# Sheet2.net
KiCad netlist of a schematic drawn in Altium Designer
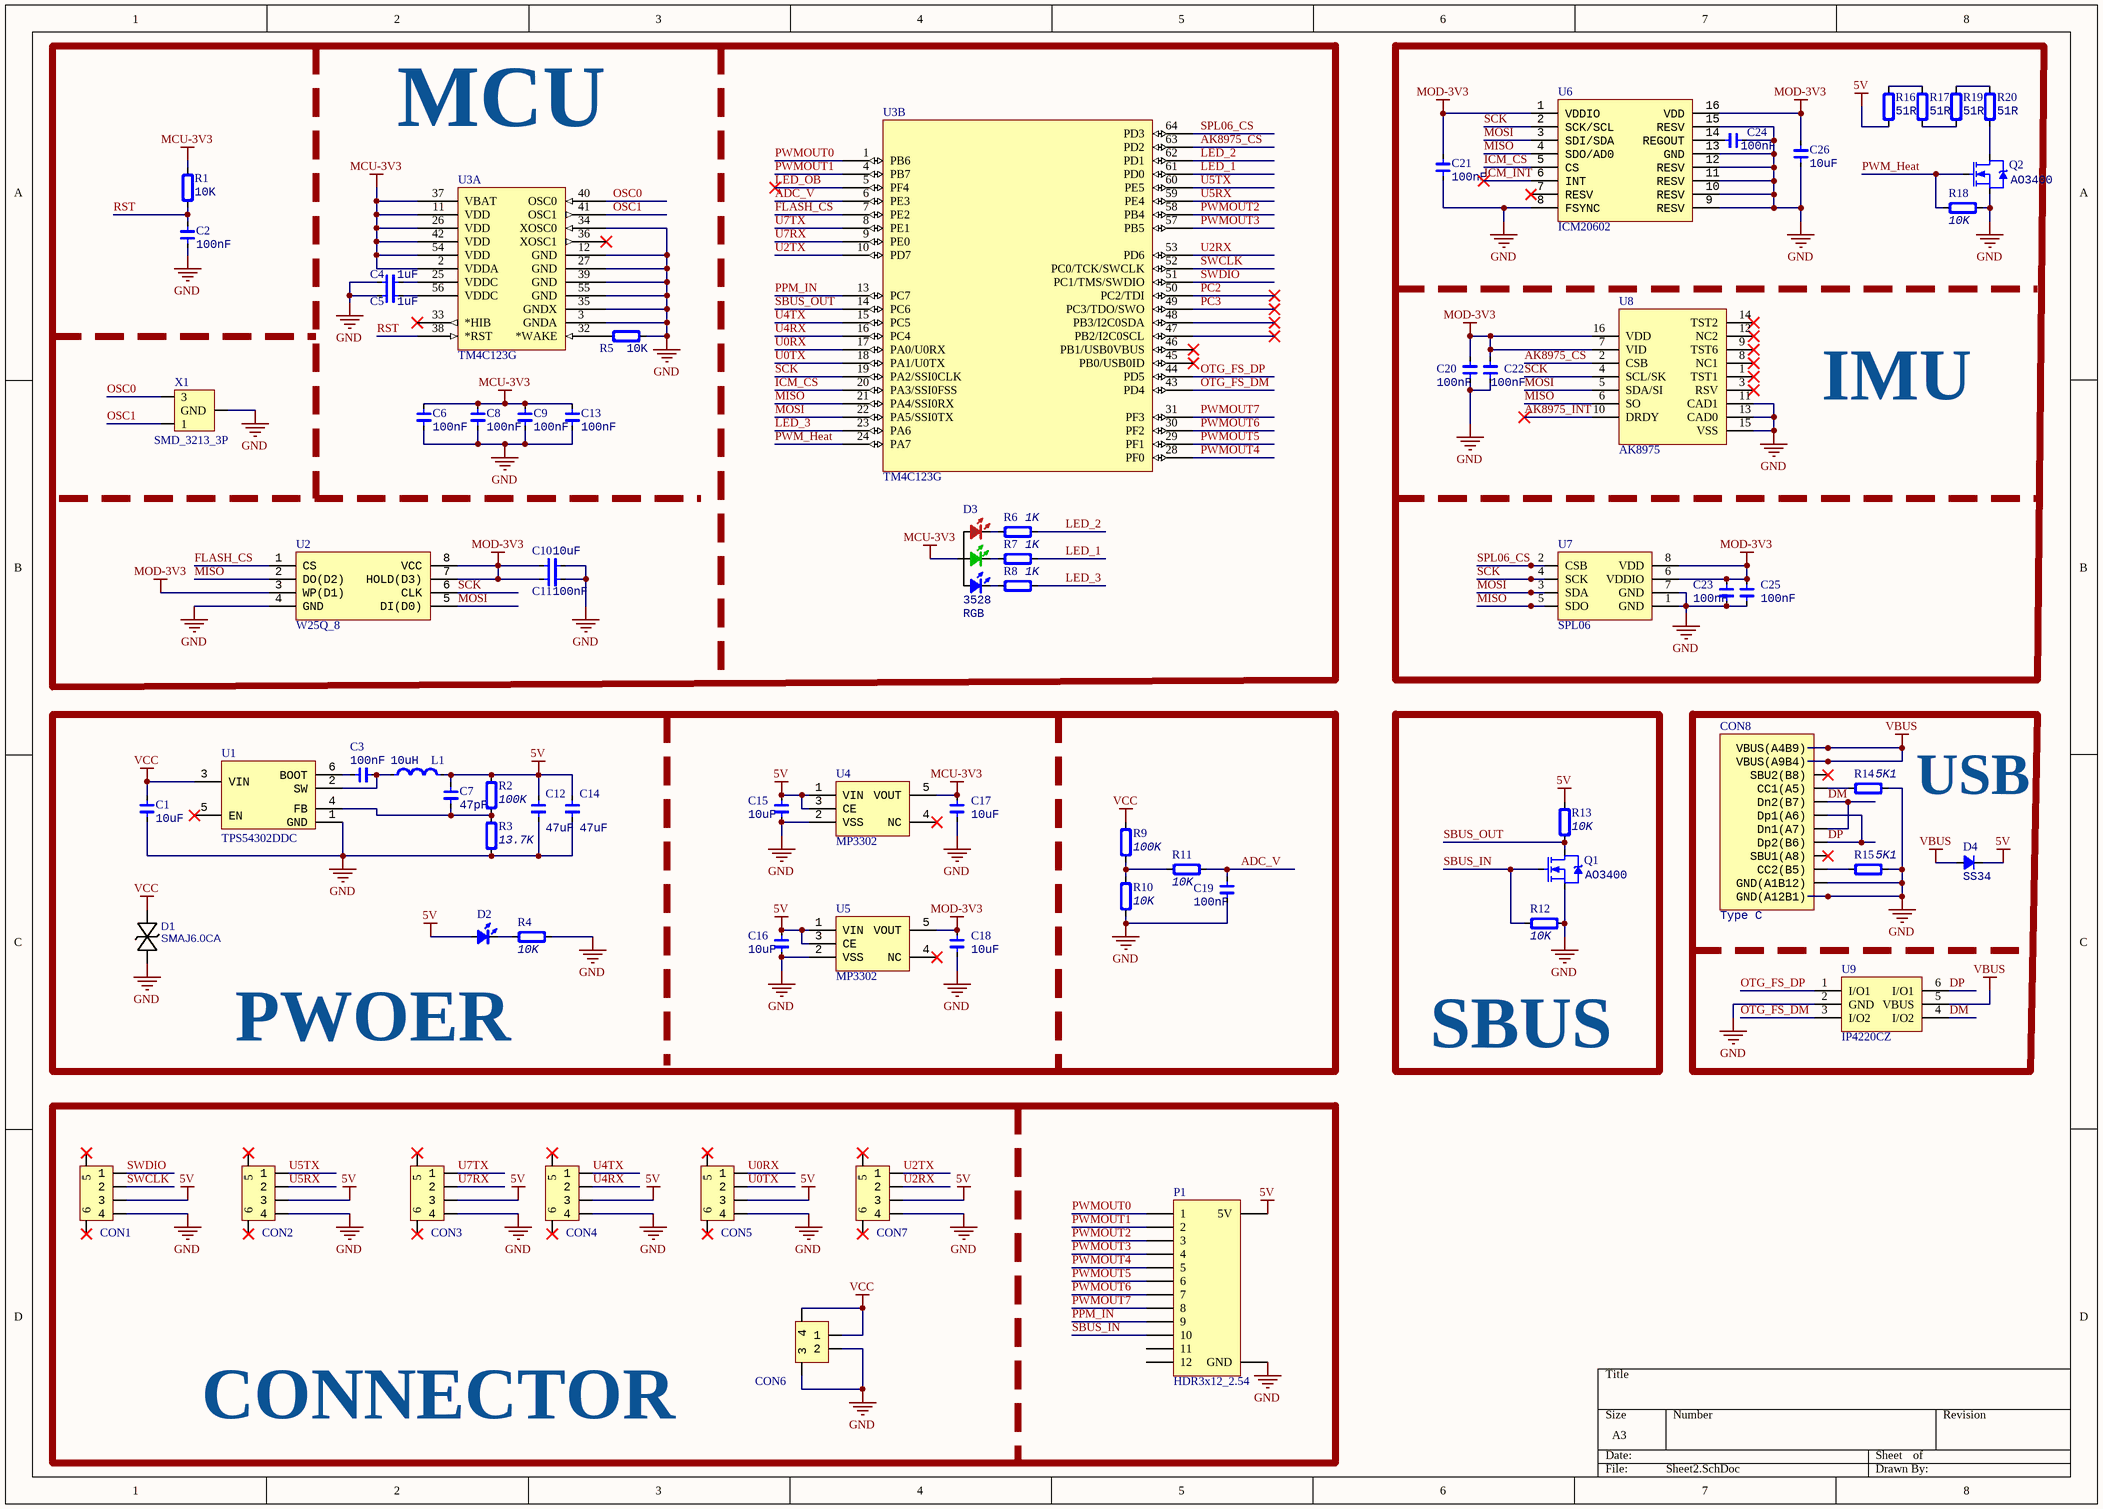
[diagram p0: Sheet2.SchDoc]

(export (version "E")
  (design (tool "Eeschema 10.0.6"))
  (components
    (comp (ref "C1")
      (value "10uF")
      (footprint "PCB_PassiveCap:CAP_0805")
      (description "Capacitor")
      (fields (field (name "Comment") "C0805"))
      (libsource (lib "SCH_Passive") (part "Cap_0805"))
    )
    (comp (ref "C2")
      (value "100nF")
      (footprint "PCB_PassiveCap:CAP_0603")
      (description "Capacitor")
      (fields (field (name "Comment") "C0603"))
      (libsource (lib "") (part "Cap_0603_1"))
    )
    (comp (ref "C3")
      (value "100nF")
      (footprint "PCB_PassiveCap:CAP_0603")
      (description "Capacitor")
      (fields (field (name "Comment") "C0603"))
      (libsource (lib "SCH_Passive") (part "Cap_0603"))
    )
    (comp (ref "C4")
      (value "1uF")
      (footprint "PCB_PassiveCap:CAP_0603")
      (description "Capacitor")
      (fields (field (name "Comment") "C0603"))
      (libsource (lib "SCH_Passive") (part "Cap_0603"))
    )
    (comp (ref "C5")
      (value "1uF")
      (footprint "PCB_PassiveCap:CAP_0603")
      (description "Capacitor")
      (fields (field (name "Comment") "C0603"))
      (libsource (lib "SCH_Passive") (part "Cap_0603"))
    )
    (comp (ref "C6")
      (value "100nF")
      (footprint "PCB_PassiveCap:CAP_0603")
      (description "Capacitor")
      (fields (field (name "Comment") "C0603"))
      (libsource (lib "") (part "Cap_0603_1"))
    )
    (comp (ref "C7")
      (value "47pF")
      (footprint "PCB_PassiveCap:CAP_0603")
      (description "Capacitor")
      (fields (field (name "Comment") "C0603"))
      (libsource (lib "") (part "Cap_0603_2"))
    )
    (comp (ref "C8")
      (value "100nF")
      (footprint "PCB_PassiveCap:CAP_0603")
      (description "Capacitor")
      (fields (field (name "Comment") "C0603"))
      (libsource (lib "") (part "Cap_0603_1"))
    )
    (comp (ref "C9")
      (value "100nF")
      (footprint "PCB_PassiveCap:CAP_0603")
      (description "Capacitor")
      (fields (field (name "Comment") "C0603"))
      (libsource (lib "") (part "Cap_0603_1"))
    )
    (comp (ref "C10")
      (value "10uF")
      (footprint "PCB_PassiveCap:CAP_0603")
      (description "Capacitor")
      (fields (field (name "Comment") "C0603"))
      (libsource (lib "") (part "Cap_0603_3"))
    )
    (comp (ref "C11")
      (value "100nF")
      (footprint "PCB_PassiveCap:CAP_0603")
      (description "Capacitor")
      (fields (field (name "Comment") "C0603"))
      (libsource (lib "SCH_Passive") (part "Cap_0603"))
    )
    (comp (ref "C12")
      (value "47uF")
      (footprint "PCB_PassiveCap:CAP_0603")
      (description "Capacitor")
      (fields (field (name "Comment") "C0603"))
      (libsource (lib "") (part "Cap_0603_1"))
    )
    (comp (ref "C13")
      (value "100nF")
      (footprint "PCB_PassiveCap:CAP_0603")
      (description "Capacitor")
      (fields (field (name "Comment") "C0603"))
      (libsource (lib "") (part "Cap_0603_1"))
    )
    (comp (ref "C14")
      (value "47uF")
      (footprint "PCB_PassiveCap:CAP_0603")
      (description "Capacitor")
      (fields (field (name "Comment") "C0603"))
      (libsource (lib "") (part "Cap_0603_1"))
    )
    (comp (ref "C15")
      (value "10uF")
      (footprint "PCB_PassiveCap:CAP_0603")
      (description "Capacitor")
      (fields (field (name "Comment") "C0603"))
      (libsource (lib "") (part "Cap_0603_1"))
    )
    (comp (ref "C16")
      (value "10uF")
      (footprint "PCB_PassiveCap:CAP_0603")
      (description "Capacitor")
      (fields (field (name "Comment") "C0603"))
      (libsource (lib "") (part "Cap_0603_1"))
    )
    (comp (ref "C17")
      (value "10uF")
      (footprint "PCB_PassiveCap:CAP_0603")
      (description "Capacitor")
      (fields (field (name "Comment") "C0603"))
      (libsource (lib "") (part "Cap_0603_1"))
    )
    (comp (ref "C18")
      (value "10uF")
      (footprint "PCB_PassiveCap:CAP_0603")
      (description "Capacitor")
      (fields (field (name "Comment") "C0603"))
      (libsource (lib "") (part "Cap_0603_1"))
    )
    (comp (ref "C19")
      (value "100nF")
      (footprint "PCB_PassiveCap:CAP_0603")
      (description "Capacitor")
      (fields (field (name "Comment") "C0603"))
      (libsource (lib "") (part "Cap_0603_2"))
    )
    (comp (ref "C20")
      (value "100nF")
      (footprint "PCB_PassiveCap:CAP_0603")
      (description "Capacitor")
      (fields (field (name "Comment") "C0603"))
      (libsource (lib "") (part "Cap_0603_2"))
    )
    (comp (ref "C21")
      (value "100nF")
      (footprint "PCB_PassiveCap:CAP_0603")
      (description "Capacitor")
      (fields (field (name "Comment") "C0603"))
      (libsource (lib "") (part "Cap_0603_2"))
    )
    (comp (ref "C22")
      (value "100nF")
      (footprint "PCB_PassiveCap:CAP_0603")
      (description "Capacitor")
      (fields (field (name "Comment") "C0603"))
      (libsource (lib "") (part "Cap_0603_2"))
    )
    (comp (ref "C23")
      (value "100nF")
      (footprint "PCB_PassiveCap:CAP_0603")
      (description "Capacitor")
      (fields (field (name "Comment") "C0603"))
      (libsource (lib "") (part "Cap_0603_2"))
    )
    (comp (ref "C24")
      (value "100nF")
      (footprint "PCB_PassiveCap:CAP_0603")
      (description "Capacitor")
      (fields (field (name "Comment") "C0603"))
      (libsource (lib "SCH_Passive") (part "Cap_0603"))
    )
    (comp (ref "C25")
      (value "100nF")
      (footprint "PCB_PassiveCap:CAP_0603")
      (description "Capacitor")
      (fields (field (name "Comment") "C0603"))
      (libsource (lib "") (part "Cap_0603_2"))
    )
    (comp (ref "C26")
      (value "10uF")
      (footprint "PCB_PassiveCap:CAP_0603")
      (description "Capacitor")
      (fields (field (name "Comment") "C0603"))
      (libsource (lib "") (part "Cap_0603_2"))
    )
    (comp (ref "CON1")
      (value "GH1.25_4P")
      (footprint "GH1.25_4P卧贴")
      (description "GH")
      (libsource (lib "SCH_Connector") (part "GH1.25_4P"))
    )
    (comp (ref "CON2")
      (value "GH1.25_4P")
      (footprint "GH1.25_4P卧贴")
      (description "GH")
      (libsource (lib "SCH_Connector") (part "GH1.25_4P"))
    )
    (comp (ref "CON3")
      (value "GH1.25_4P")
      (footprint "GH1.25_4P卧贴")
      (description "GH")
      (libsource (lib "SCH_Connector") (part "GH1.25_4P"))
    )
    (comp (ref "CON4")
      (value "GH1.25_4P")
      (footprint "GH1.25_4P卧贴")
      (description "GH")
      (libsource (lib "SCH_Connector") (part "GH1.25_4P"))
    )
    (comp (ref "CON5")
      (value "GH1.25_4P")
      (footprint "GH1.25_4P卧贴")
      (description "GH")
      (libsource (lib "SCH_Connector") (part "GH1.25_4P"))
    )
    (comp (ref "CON6")
      (value "GH1.25_2P")
      (footprint "GH1.25-2P")
      (description "GH")
      (libsource (lib "SCH_Connector") (part "GH1.25_2P"))
    )
    (comp (ref "CON7")
      (value "GH1.25_4P")
      (footprint "GH1.25_4P卧贴")
      (description "GH")
      (libsource (lib "SCH_Connector") (part "GH1.25_4P"))
    )
    (comp (ref "CON8")
      (value "Type C")
      (footprint "USB_TypeC_SMD_16P")
      (description "USB")
      (fields (field (name "Comment") "USB Type C"))
      (libsource (lib "SCH_USB") (part "USB_TypeC_16P"))
    )
    (comp (ref "D1")
      (value "SMAJ6.0CA")
      (footprint "DO-214AC")
      (description "SMAJ6.0CA_C698928")
      (fields (field (name "BOM_SUPPLIER PART") "C698928") (field (name "CONTRIBUTOR") "LCSC"))
      (libsource (lib "封装库") (part "SMAJ6.0CA"))
    )
    (comp (ref "D2")
      (value "D0603")
      (footprint "PCB_ActiveLED:LED_0603_RED")
      (description "LED")
      (libsource (lib "SCH_Active") (part "LED_0603"))
    )
    (comp (ref "D3")
      (value "RGB")
      (footprint "PCB_ActiveLED:LED_3528_RGB")
      (description "LED")
      (fields (field (name "TYPE") "3528") (field (name "Comment") "D3528"))
      (libsource (lib "SCH_Active") (part "LED_3528_RGB"))
    )
    (comp (ref "D4")
      (value "SS34")
      (footprint "PCB_ActiveDIO:DO-214AC")
      (description "Diode")
      (libsource (lib "SCH_Active") (part "Diode_SMA"))
    )
    (comp (ref "L1")
      (value "10uH")
      (footprint "IND_0630")
      (description "Inductor")
      (fields (field (name "Comment") "H1008"))
      (libsource (lib "SCH_Passive") (part "Ind_0630"))
    )
    (comp (ref "P1")
      (value "HDR3x12_2.54")
      (footprint "HDR3x12_2.54")
      (libsource (lib "SCH_ConnectorHDR") (part "HDR3x12_2.54"))
    )
    (comp (ref "Q1")
      (value "AO3400")
      (footprint "SOT23-3")
      (description "MOSFET")
      (libsource (lib "SCH_Active") (part "MOSFET_N"))
    )
    (comp (ref "Q2")
      (value "AO3400")
      (footprint "SOT23-3")
      (description "MOSFET")
      (libsource (lib "SCH_Active") (part "MOSFET_N"))
    )
    (comp (ref "R1")
      (value "10K")
      (footprint "PCB_PassiveRes:RES_0603")
      (description "Resistor")
      (fields (field (name "Comment") "R0603"))
      (libsource (lib "SCH_Passive") (part "Res_0603"))
    )
    (comp (ref "R2")
      (value "100K")
      (footprint "PCB_PassiveRes:RES_0603")
      (description "Resistor")
      (fields (field (name "Comment") "R0603"))
      (libsource (lib "SCH_Passive") (part "Res_0603"))
    )
    (comp (ref "R3")
      (value "13.7K")
      (footprint "PCB_PassiveRes:RES_0603")
      (description "Resistor")
      (fields (field (name "Comment") "R0603"))
      (libsource (lib "SCH_Passive") (part "Res_0603"))
    )
    (comp (ref "R4")
      (value "10K")
      (footprint "PCB_PassiveRes:RES_0603")
      (description "Resistor")
      (fields (field (name "Comment") "R0603"))
      (libsource (lib "SCH_Passive") (part "Res_0603"))
    )
    (comp (ref "R5")
      (value "10K")
      (footprint "PCB_PassiveRes:RES_0603")
      (description "Resistor")
      (fields (field (name "Comment") "R0603"))
      (libsource (lib "SCH_Passive") (part "Res_0603"))
    )
    (comp (ref "R6")
      (value "1K")
      (footprint "PCB_PassiveRes:RES_0603")
      (description "Resistor")
      (fields (field (name "Comment") "R0603"))
      (libsource (lib "SCH_Passive") (part "Res_0603"))
    )
    (comp (ref "R7")
      (value "1K")
      (footprint "PCB_PassiveRes:RES_0603")
      (description "Resistor")
      (fields (field (name "Comment") "R0603"))
      (libsource (lib "SCH_Passive") (part "Res_0603"))
    )
    (comp (ref "R8")
      (value "1K")
      (footprint "PCB_PassiveRes:RES_0603")
      (description "Resistor")
      (fields (field (name "Comment") "R0603"))
      (libsource (lib "SCH_Passive") (part "Res_0603"))
    )
    (comp (ref "R9")
      (value "100K")
      (footprint "PCB_PassiveRes:RES_0603")
      (description "Resistor")
      (fields (field (name "Comment") "R0603"))
      (libsource (lib "SCH_Passive") (part "Res_0603"))
    )
    (comp (ref "R10")
      (value "10K")
      (footprint "PCB_PassiveRes:RES_0603")
      (description "Resistor")
      (fields (field (name "Comment") "R0603"))
      (libsource (lib "SCH_Passive") (part "Res_0603"))
    )
    (comp (ref "R11")
      (value "10K")
      (footprint "PCB_PassiveRes:RES_0603")
      (description "Resistor")
      (fields (field (name "Comment") "R0603"))
      (libsource (lib "SCH_Passive") (part "Res_0603"))
    )
    (comp (ref "R12")
      (value "10K")
      (footprint "PCB_PassiveRes:RES_0603")
      (description "Resistor")
      (fields (field (name "Comment") "R0603"))
      (libsource (lib "SCH_Passive") (part "Res_0603"))
    )
    (comp (ref "R13")
      (value "10K")
      (footprint "PCB_PassiveRes:RES_0603")
      (description "Resistor")
      (fields (field (name "Comment") "R0603"))
      (libsource (lib "SCH_Passive") (part "Res_0603"))
    )
    (comp (ref "R14")
      (value "5K1")
      (footprint "PCB_PassiveRes:RES_0603")
      (description "Resistor")
      (fields (field (name "Comment") "R0603"))
      (libsource (lib "SCH_Passive") (part "Res_0603"))
    )
    (comp (ref "R15")
      (value "5K1")
      (footprint "PCB_PassiveRes:RES_0603")
      (description "Resistor")
      (fields (field (name "Comment") "R0603"))
      (libsource (lib "SCH_Passive") (part "Res_0603"))
    )
    (comp (ref "R16")
      (value "51R")
      (footprint "PCB_PassiveRes:RES_0805")
      (description "Resistor")
      (fields (field (name "Comment") "R0805"))
      (libsource (lib "SCH_Passive") (part "Res_0805"))
    )
    (comp (ref "R17")
      (value "51R")
      (footprint "PCB_PassiveRes:RES_0805")
      (description "Resistor")
      (fields (field (name "Comment") "R0805"))
      (libsource (lib "SCH_Passive") (part "Res_0805"))
    )
    (comp (ref "R18")
      (value "10K")
      (footprint "PCB_PassiveRes:RES_0603")
      (description "Resistor")
      (fields (field (name "Comment") "R0603"))
      (libsource (lib "SCH_Passive") (part "Res_0603"))
    )
    (comp (ref "R19")
      (value "51R")
      (footprint "PCB_PassiveRes:RES_0805")
      (description "Resistor")
      (fields (field (name "Comment") "R0805"))
      (libsource (lib "SCH_Passive") (part "Res_0805"))
    )
    (comp (ref "R20")
      (value "51R")
      (footprint "PCB_PassiveRes:RES_0805")
      (description "Resistor")
      (fields (field (name "Comment") "R0805"))
      (libsource (lib "SCH_Passive") (part "Res_0805"))
    )
    (comp (ref "U1")
      (value "TPS54302DDC")
      (footprint "SOT23-6")
      (description "Power")
      (libsource (lib "SCH_Power") (part "TPS54302DDC"))
    )
    (comp (ref "U2")
      (value "W25Q_8")
      (footprint "PCB_IntegratedCircuit:SON_P1.27H_8")
      (description "FLASH")
      (libsource (lib "SCH_IntegratedCircuit") (part "W25Q_8"))
    )
    (comp (ref "U3")
      (value "TM4C123G")
      (footprint "LQFP_P0.5_64")
      (libsource (lib "SCH_Microcontroller") (part "TM4C123G"))
    )
    (comp (ref "U4")
      (value "MP3302")
      (footprint "PCB_IntegratedCircuit:SOT23-5")
      (description "WLED Driver")
      (libsource (lib "SCH_Power") (part "HX9133"))
    )
    (comp (ref "U5")
      (value "MP3302")
      (footprint "PCB_IntegratedCircuit:SOT23-5")
      (description "WLED Driver")
      (libsource (lib "SCH_Power") (part "HX9133"))
    )
    (comp (ref "U6")
      (value "ICM20602")
      (footprint "LGA_P0.5_16")
      (description "Sensor Motion")
      (libsource (lib "SCH_Sensor") (part "ICM20602"))
    )
    (comp (ref "U7") (value "SPL06") (footprint "SMD_8P-2x2.5") (libsource (lib "SCH_Sensor") (part "SPL06")))
    (comp (ref "U8")
      (value "AK8975")
      (footprint "QFN_P0.65_16")
      (libsource (lib "SCH_Sensor") (part "AK8975"))
    )
    (comp (ref "U9") (value "IP4220CZ") (footprint "SOT23-6") (libsource (lib "SCH_USB") (part "USB_ESD")))
    (comp (ref "X1")
      (value "SMD_3213_3P")
      (footprint "XT_3213_3")
      (description "Crystal Oscillator")
      (libsource (lib "SCH_Oscillator") (part "SMD_3213_3P"))
    )
  )
  (nets
    (net (code "1") (name "/ADC_V") (class "Default")
      (node (ref "C19") (pin "1") (pinfunction "1_1") (pintype "passive"))
      (node (ref "R11") (pin "1") (pinfunction "1_1") (pintype "passive"))
      (node (ref "U3") (pin "6") (pinfunction "PE3_6") (pintype "bidirectional"))
    )
    (net (code "2") (name "/AK8975_CS") (class "Default")
      (node (ref "U3") (pin "63") (pinfunction "PD2_63") (pintype "bidirectional"))
      (node (ref "U8") (pin "2") (pinfunction "CSB_2") (pintype "passive"))
    )
    (net (code "3") (name "/AK8975_INT") (class "Default")
      (node (ref "U8") (pin "10") (pinfunction "DRDY_10") (pintype "passive+no_connect"))
    )
    (net (code "4") (name "/DM") (class "Default")
      (node (ref "CON8") (pin "5") (pinfunction "Dn2(B7)_5") (pintype "passive"))
      (node (ref "CON8") (pin "7") (pinfunction "Dn1(A7)_7") (pintype "passive"))
      (node (ref "U9") (pin "4") (pinfunction "I/O2_4") (pintype "passive"))
    )
    (net (code "5") (name "/DP") (class "Default")
      (node (ref "CON8") (pin "6") (pinfunction "Dp1(A6)_6") (pintype "passive"))
      (node (ref "CON8") (pin "8") (pinfunction "Dp2(B6)_8") (pintype "passive"))
      (node (ref "U9") (pin "6") (pinfunction "I/O1_6") (pintype "passive"))
    )
    (net (code "6") (name "/FLASH_CS") (class "Default")
      (node (ref "U2") (pin "1") (pinfunction "CS_1") (pintype "passive"))
      (node (ref "U3") (pin "7") (pinfunction "PE2_7") (pintype "bidirectional"))
    )
    (net (code "7") (name "/ICM_CS") (class "Default")
      (node (ref "U3") (pin "20") (pinfunction "PA3/SSI0FSS_20") (pintype "bidirectional"))
      (node (ref "U6") (pin "5") (pinfunction "CS_5") (pintype "passive"))
    )
    (net (code "8") (name "/ICM_INT") (class "Default")
      (node (ref "U6") (pin "6") (pinfunction "INT_6") (pintype "passive+no_connect"))
    )
    (net (code "9") (name "/LED_1") (class "Default")
      (node (ref "R7") (pin "1") (pinfunction "1_1") (pintype "passive"))
      (node (ref "U3") (pin "61") (pinfunction "PD0_61") (pintype "bidirectional"))
    )
    (net (code "10") (name "/LED_2") (class "Default")
      (node (ref "R6") (pin "1") (pinfunction "1_1") (pintype "passive"))
      (node (ref "U3") (pin "62") (pinfunction "PD1_62") (pintype "bidirectional"))
    )
    (net (code "11") (name "/LED_3") (class "Default")
      (node (ref "R8") (pin "1") (pinfunction "1_1") (pintype "passive"))
      (node (ref "U3") (pin "23") (pinfunction "PA6_23") (pintype "bidirectional"))
    )
    (net (code "12") (name "/LED_OB") (class "Default")
      (node (ref "U3") (pin "5") (pinfunction "PF4_5") (pintype "bidirectional+no_connect"))
    )
    (net (code "13") (name "/MISO") (class "Default")
      (node (ref "U2") (pin "2") (pinfunction "DO(D2)_2") (pintype "passive"))
      (node (ref "U3") (pin "21") (pinfunction "PA4/SSI0RX_21") (pintype "bidirectional"))
      (node (ref "U6") (pin "4") (pinfunction "SDO/AD0_4") (pintype "passive"))
      (node (ref "U7") (pin "5") (pinfunction "SDO_5") (pintype "passive"))
      (node (ref "U8") (pin "6") (pinfunction "SO_6") (pintype "passive"))
    )
    (net (code "14") (name "/MOSI") (class "Default")
      (node (ref "U2") (pin "5") (pinfunction "DI(D0)_5") (pintype "passive"))
      (node (ref "U3") (pin "22") (pinfunction "PA5/SSI0TX_22") (pintype "bidirectional"))
      (node (ref "U6") (pin "3") (pinfunction "SDI/SDA_3") (pintype "passive"))
      (node (ref "U7") (pin "3") (pinfunction "SDA_3") (pintype "passive"))
      (node (ref "U8") (pin "5") (pinfunction "SDA/SI_5") (pintype "passive"))
    )
    (net (code "15") (name "/OSC0") (class "Default")
      (node (ref "U3") (pin "40") (pinfunction "OSC0_40") (pintype "input"))
      (node (ref "X1") (pin "3") (pinfunction "3_3") (pintype "passive"))
    )
    (net (code "16") (name "/OSC1") (class "Default")
      (node (ref "U3") (pin "41") (pinfunction "OSC1_41") (pintype "output"))
      (node (ref "X1") (pin "1") (pinfunction "1_1") (pintype "passive"))
    )
    (net (code "17") (name "/OTG_FS_DM") (class "Default")
      (node (ref "U3") (pin "43") (pinfunction "PD4_43") (pintype "bidirectional"))
      (node (ref "U9") (pin "3") (pinfunction "I/O2_3") (pintype "passive"))
    )
    (net (code "18") (name "/OTG_FS_DP") (class "Default")
      (node (ref "U3") (pin "44") (pinfunction "PD5_44") (pintype "bidirectional"))
      (node (ref "U9") (pin "1") (pinfunction "I/O1_1") (pintype "passive"))
    )
    (net (code "19") (name "/PC2") (class "Default")
      (node (ref "U3") (pin "50") (pinfunction "PC2/TDI_50") (pintype "bidirectional+no_connect"))
    )
    (net (code "20") (name "/PC3") (class "Default")
      (node (ref "U3") (pin "49") (pinfunction "PC3/TDO/SWO_49") (pintype "bidirectional+no_connect"))
    )
    (net (code "21") (name "/PPM_IN") (class "Default")
      (node (ref "P1") (pin "9") (pinfunction "9_9") (pintype "passive"))
      (node (ref "U3") (pin "13") (pinfunction "PC7_13") (pintype "bidirectional"))
    )
    (net (code "22") (name "/PWMOUT0") (class "Default")
      (node (ref "P1") (pin "1") (pinfunction "1_1") (pintype "passive"))
      (node (ref "U3") (pin "1") (pinfunction "PB6_1") (pintype "bidirectional"))
    )
    (net (code "23") (name "/PWMOUT1") (class "Default")
      (node (ref "P1") (pin "2") (pinfunction "2_2") (pintype "passive"))
      (node (ref "U3") (pin "4") (pinfunction "PB7_4") (pintype "bidirectional"))
    )
    (net (code "24") (name "/PWMOUT2") (class "Default")
      (node (ref "P1") (pin "3") (pinfunction "3_3") (pintype "passive"))
      (node (ref "U3") (pin "58") (pinfunction "PB4_58") (pintype "bidirectional"))
    )
    (net (code "25") (name "/PWMOUT3") (class "Default")
      (node (ref "P1") (pin "4") (pinfunction "4_4") (pintype "passive"))
      (node (ref "U3") (pin "57") (pinfunction "PB5_57") (pintype "bidirectional"))
    )
    (net (code "26") (name "/PWMOUT4") (class "Default")
      (node (ref "P1") (pin "5") (pinfunction "5_5") (pintype "passive"))
      (node (ref "U3") (pin "28") (pinfunction "PF0_28") (pintype "bidirectional"))
    )
    (net (code "27") (name "/PWMOUT5") (class "Default")
      (node (ref "P1") (pin "6") (pinfunction "6_6") (pintype "passive"))
      (node (ref "U3") (pin "29") (pinfunction "PF1_29") (pintype "bidirectional"))
    )
    (net (code "28") (name "/PWMOUT6") (class "Default")
      (node (ref "P1") (pin "7") (pinfunction "7_7") (pintype "passive"))
      (node (ref "U3") (pin "30") (pinfunction "PF2_30") (pintype "bidirectional"))
    )
    (net (code "29") (name "/PWMOUT7") (class "Default")
      (node (ref "P1") (pin "8") (pinfunction "8_8") (pintype "passive"))
      (node (ref "U3") (pin "31") (pinfunction "PF3_31") (pintype "bidirectional"))
    )
    (net (code "30") (name "/PWM_Heat") (class "Default")
      (node (ref "Q2") (pin "2") (pinfunction "G_2") (pintype "passive"))
      (node (ref "R18") (pin "1") (pinfunction "1_1") (pintype "passive"))
      (node (ref "U3") (pin "24") (pinfunction "PA7_24") (pintype "bidirectional"))
    )
    (net (code "31") (name "/RST") (class "Default")
      (node (ref "C2") (pin "2") (pinfunction "2_2") (pintype "passive"))
      (node (ref "R1") (pin "1") (pinfunction "1_1") (pintype "passive"))
      (node (ref "U3") (pin "38") (pinfunction "*RST_38") (pintype "input"))
    )
    (net (code "32") (name "/SBUS_IN") (class "Default")
      (node (ref "P1") (pin "10") (pinfunction "10_10") (pintype "passive"))
      (node (ref "Q1") (pin "2") (pinfunction "G_2") (pintype "passive"))
      (node (ref "R12") (pin "1") (pinfunction "1_1") (pintype "passive"))
    )
    (net (code "33") (name "/SBUS_OUT") (class "Default")
      (node (ref "Q1") (pin "3") (pinfunction "D_3") (pintype "passive"))
      (node (ref "R13") (pin "1") (pinfunction "1_1") (pintype "passive"))
      (node (ref "U3") (pin "14") (pinfunction "PC6_14") (pintype "bidirectional"))
    )
    (net (code "34") (name "/SCK") (class "Default")
      (node (ref "U2") (pin "6") (pinfunction "CLK_6") (pintype "passive"))
      (node (ref "U3") (pin "19") (pinfunction "PA2/SSI0CLK_19") (pintype "bidirectional"))
      (node (ref "U6") (pin "2") (pinfunction "SCK/SCL_2") (pintype "passive"))
      (node (ref "U7") (pin "4") (pinfunction "SCK_4") (pintype "passive"))
      (node (ref "U8") (pin "4") (pinfunction "SCL/SK_4") (pintype "passive"))
    )
    (net (code "35") (name "/SPL06_CS") (class "Default")
      (node (ref "U3") (pin "64") (pinfunction "PD3_64") (pintype "bidirectional"))
      (node (ref "U7") (pin "2") (pinfunction "CSB_2") (pintype "passive"))
    )
    (net (code "36") (name "/SWCLK") (class "Default")
      (node (ref "CON1") (pin "2") (pinfunction "2_2") (pintype "passive"))
      (node (ref "U3") (pin "52") (pinfunction "PC0/TCK/SWCLK_52") (pintype "bidirectional"))
    )
    (net (code "37") (name "/SWDIO") (class "Default")
      (node (ref "CON1") (pin "1") (pinfunction "1_1") (pintype "passive"))
      (node (ref "U3") (pin "51") (pinfunction "PC1/TMS/SWDIO_51") (pintype "bidirectional"))
    )
    (net (code "38") (name "/U0RX") (class "Default")
      (node (ref "CON5") (pin "1") (pinfunction "1_1") (pintype "passive"))
      (node (ref "U3") (pin "17") (pinfunction "PA0/U0RX_17") (pintype "bidirectional"))
    )
    (net (code "39") (name "/U0TX") (class "Default")
      (node (ref "CON5") (pin "2") (pinfunction "2_2") (pintype "passive"))
      (node (ref "U3") (pin "18") (pinfunction "PA1/U0TX_18") (pintype "bidirectional"))
    )
    (net (code "40") (name "/U2RX") (class "Default")
      (node (ref "CON7") (pin "2") (pinfunction "2_2") (pintype "passive"))
      (node (ref "U3") (pin "53") (pinfunction "PD6_53") (pintype "bidirectional"))
    )
    (net (code "41") (name "/U2TX") (class "Default")
      (node (ref "CON7") (pin "1") (pinfunction "1_1") (pintype "passive"))
      (node (ref "U3") (pin "10") (pinfunction "PD7_10") (pintype "bidirectional"))
    )
    (net (code "42") (name "/U4RX") (class "Default")
      (node (ref "CON4") (pin "2") (pinfunction "2_2") (pintype "passive"))
      (node (ref "U3") (pin "16") (pinfunction "PC4_16") (pintype "bidirectional"))
    )
    (net (code "43") (name "/U4TX") (class "Default")
      (node (ref "CON4") (pin "1") (pinfunction "1_1") (pintype "passive"))
      (node (ref "U3") (pin "15") (pinfunction "PC5_15") (pintype "bidirectional"))
    )
    (net (code "44") (name "/U5RX") (class "Default")
      (node (ref "CON2") (pin "2") (pinfunction "2_2") (pintype "passive"))
      (node (ref "U3") (pin "59") (pinfunction "PE4_59") (pintype "bidirectional"))
    )
    (net (code "45") (name "/U5TX") (class "Default")
      (node (ref "CON2") (pin "1") (pinfunction "1_1") (pintype "passive"))
      (node (ref "U3") (pin "60") (pinfunction "PE5_60") (pintype "bidirectional"))
    )
    (net (code "46") (name "/U7RX") (class "Default")
      (node (ref "CON3") (pin "2") (pinfunction "2_2") (pintype "passive"))
      (node (ref "U3") (pin "9") (pinfunction "PE0_9") (pintype "bidirectional"))
    )
    (net (code "47") (name "/U7TX") (class "Default")
      (node (ref "CON3") (pin "1") (pinfunction "1_1") (pintype "passive"))
      (node (ref "U3") (pin "8") (pinfunction "PE1_8") (pintype "bidirectional"))
    )
    (net (code "48") (name "5V") (class "Default")
      (node (ref "C12") (pin "2") (pinfunction "2_2") (pintype "passive"))
      (node (ref "C14") (pin "2") (pinfunction "2_2") (pintype "passive"))
      (node (ref "C15") (pin "2") (pinfunction "2_2") (pintype "passive"))
      (node (ref "C16") (pin "2") (pinfunction "2_2") (pintype "passive"))
      (node (ref "C7") (pin "1") (pinfunction "1_1") (pintype "passive"))
      (node (ref "CON1") (pin "3") (pinfunction "3_3") (pintype "passive"))
      (node (ref "CON2") (pin "3") (pinfunction "3_3") (pintype "passive"))
      (node (ref "CON3") (pin "3") (pinfunction "3_3") (pintype "passive"))
      (node (ref "CON4") (pin "3") (pinfunction "3_3") (pintype "passive"))
      (node (ref "CON5") (pin "3") (pinfunction "3_3") (pintype "passive"))
      (node (ref "CON7") (pin "3") (pinfunction "3_3") (pintype "passive"))
      (node (ref "D2") (pin "1") (pinfunction "A_1") (pintype "passive"))
      (node (ref "D4") (pin "2") (pinfunction "K_2") (pintype "passive"))
      (node (ref "L1") (pin "2") (pinfunction "2_2") (pintype "passive"))
      (node (ref "P1") (pin "13") (pinfunction "5V_13") (pintype "passive"))
      (node (ref "R13") (pin "2") (pinfunction "2_2") (pintype "passive"))
      (node (ref "R16") (pin "1") (pinfunction "1_1") (pintype "passive"))
      (node (ref "R2") (pin "2") (pinfunction "2_2") (pintype "passive"))
      (node (ref "U4") (pin "1") (pinfunction "VIN_1") (pintype "passive"))
      (node (ref "U4") (pin "3") (pinfunction "CE_3") (pintype "passive"))
      (node (ref "U5") (pin "1") (pinfunction "VIN_1") (pintype "passive"))
      (node (ref "U5") (pin "3") (pinfunction "CE_3") (pintype "passive"))
    )
    (net (code "49") (name "GND") (class "Default")
      (node (ref "C1") (pin "1") (pinfunction "1_1") (pintype "passive"))
      (node (ref "C10") (pin "2") (pinfunction "2_2") (pintype "passive"))
      (node (ref "C11") (pin "1") (pinfunction "1_1") (pintype "passive"))
      (node (ref "C12") (pin "1") (pinfunction "1_1") (pintype "passive"))
      (node (ref "C13") (pin "1") (pinfunction "1_1") (pintype "passive"))
      (node (ref "C14") (pin "1") (pinfunction "1_1") (pintype "passive"))
      (node (ref "C15") (pin "1") (pinfunction "1_1") (pintype "passive"))
      (node (ref "C16") (pin "1") (pinfunction "1_1") (pintype "passive"))
      (node (ref "C17") (pin "1") (pinfunction "1_1") (pintype "passive"))
      (node (ref "C18") (pin "1") (pinfunction "1_1") (pintype "passive"))
      (node (ref "C19") (pin "2") (pinfunction "2_2") (pintype "passive"))
      (node (ref "C2") (pin "1") (pinfunction "1_1") (pintype "passive"))
      (node (ref "C20") (pin "2") (pinfunction "2_2") (pintype "passive"))
      (node (ref "C21") (pin "2") (pinfunction "2_2") (pintype "passive"))
      (node (ref "C22") (pin "2") (pinfunction "2_2") (pintype "passive"))
      (node (ref "C23") (pin "2") (pinfunction "2_2") (pintype "passive"))
      (node (ref "C24") (pin "1") (pinfunction "1_1") (pintype "passive"))
      (node (ref "C25") (pin "2") (pinfunction "2_2") (pintype "passive"))
      (node (ref "C26") (pin "2") (pinfunction "2_2") (pintype "passive"))
      (node (ref "C4") (pin "2") (pinfunction "2_2") (pintype "passive"))
      (node (ref "C5") (pin "2") (pinfunction "2_2") (pintype "passive"))
      (node (ref "C6") (pin "1") (pinfunction "1_1") (pintype "passive"))
      (node (ref "C8") (pin "1") (pinfunction "1_1") (pintype "passive"))
      (node (ref "C9") (pin "1") (pinfunction "1_1") (pintype "passive"))
      (node (ref "CON1") (pin "4") (pinfunction "4_4") (pintype "passive"))
      (node (ref "CON2") (pin "4") (pinfunction "4_4") (pintype "passive"))
      (node (ref "CON3") (pin "4") (pinfunction "4_4") (pintype "passive"))
      (node (ref "CON4") (pin "4") (pinfunction "4_4") (pintype "passive"))
      (node (ref "CON5") (pin "4") (pinfunction "4_4") (pintype "passive"))
      (node (ref "CON6") (pin "2") (pinfunction "2_2") (pintype "passive"))
      (node (ref "CON6") (pin "3") (pinfunction "3_3") (pintype "passive"))
      (node (ref "CON7") (pin "4") (pinfunction "4_4") (pintype "passive"))
      (node (ref "CON8") (pin "1") (pinfunction "GND(A1B12)_1") (pintype "passive"))
      (node (ref "CON8") (pin "12") (pinfunction "GND(A12B1)_12") (pintype "passive"))
      (node (ref "D1") (pin "1") (pinfunction "C_1") (pintype "passive"))
      (node (ref "P1") (pin "14") (pinfunction "GND_14") (pintype "passive"))
      (node (ref "Q1") (pin "1") (pinfunction "S_1") (pintype "passive"))
      (node (ref "Q2") (pin "1") (pinfunction "S_1") (pintype "passive"))
      (node (ref "R10") (pin "1") (pinfunction "1_1") (pintype "passive"))
      (node (ref "R12") (pin "2") (pinfunction "2_2") (pintype "passive"))
      (node (ref "R14") (pin "1") (pinfunction "1_1") (pintype "passive"))
      (node (ref "R15") (pin "1") (pinfunction "1_1") (pintype "passive"))
      (node (ref "R18") (pin "2") (pinfunction "2_2") (pintype "passive"))
      (node (ref "R3") (pin "1") (pinfunction "1_1") (pintype "passive"))
      (node (ref "R4") (pin "2") (pinfunction "2_2") (pintype "passive"))
      (node (ref "R5") (pin "1") (pinfunction "1_1") (pintype "passive"))
      (node (ref "U1") (pin "1") (pinfunction "GND_1") (pintype "passive"))
      (node (ref "U2") (pin "4") (pinfunction "GND_4") (pintype "passive"))
      (node (ref "U3") (pin "12") (pinfunction "GND_12") (pintype "power_in"))
      (node (ref "U3") (pin "27") (pinfunction "GND_27") (pintype "power_in"))
      (node (ref "U3") (pin "3") (pinfunction "GNDA_3") (pintype "power_in"))
      (node (ref "U3") (pin "34") (pinfunction "XOSC0_34") (pintype "input"))
      (node (ref "U3") (pin "35") (pinfunction "GNDX_35") (pintype "power_in"))
      (node (ref "U3") (pin "39") (pinfunction "GND_39") (pintype "power_in"))
      (node (ref "U3") (pin "55") (pinfunction "GND_55") (pintype "power_in"))
      (node (ref "U4") (pin "2") (pinfunction "VSS_2") (pintype "passive"))
      (node (ref "U5") (pin "2") (pinfunction "VSS_2") (pintype "passive"))
      (node (ref "U6") (pin "10") (pinfunction "RESV_10") (pintype "passive"))
      (node (ref "U6") (pin "11") (pinfunction "RESV_11") (pintype "passive"))
      (node (ref "U6") (pin "12") (pinfunction "RESV_12") (pintype "passive"))
      (node (ref "U6") (pin "13") (pinfunction "GND_13") (pintype "passive"))
      (node (ref "U6") (pin "15") (pinfunction "RESV_15") (pintype "passive"))
      (node (ref "U6") (pin "8") (pinfunction "FSYNC_8") (pintype "passive"))
      (node (ref "U6") (pin "9") (pinfunction "RESV_9") (pintype "passive"))
      (node (ref "U7") (pin "1") (pinfunction "GND_1") (pintype "passive"))
      (node (ref "U7") (pin "7") (pinfunction "GND_7") (pintype "passive"))
      (node (ref "U8") (pin "11") (pinfunction "CAD1_11") (pintype "passive"))
      (node (ref "U8") (pin "13") (pinfunction "CAD0_13") (pintype "passive"))
      (node (ref "U8") (pin "15") (pinfunction "VSS_15") (pintype "passive"))
      (node (ref "U9") (pin "2") (pinfunction "GND_2") (pintype "passive"))
      (node (ref "X1") (pin "2") (pinfunction "GND_2") (pintype "passive"))
    )
    (net (code "50") (name "MCU-3V3") (class "Default")
      (node (ref "C13") (pin "2") (pinfunction "2_2") (pintype "passive"))
      (node (ref "C17") (pin "2") (pinfunction "2_2") (pintype "passive"))
      (node (ref "C6") (pin "2") (pinfunction "2_2") (pintype "passive"))
      (node (ref "C8") (pin "2") (pinfunction "2_2") (pintype "passive"))
      (node (ref "C9") (pin "2") (pinfunction "2_2") (pintype "passive"))
      (node (ref "D3") (pin "4") (pinfunction "A_4") (pintype "passive"))
      (node (ref "R1") (pin "2") (pinfunction "2_2") (pintype "passive"))
      (node (ref "U3") (pin "11") (pinfunction "VDD_11") (pintype "power_in"))
      (node (ref "U3") (pin "2") (pinfunction "VDDA_2") (pintype "power_in"))
      (node (ref "U3") (pin "26") (pinfunction "VDD_26") (pintype "power_in"))
      (node (ref "U3") (pin "37") (pinfunction "VBAT_37") (pintype "power_in"))
      (node (ref "U3") (pin "42") (pinfunction "VDD_42") (pintype "power_in"))
      (node (ref "U3") (pin "54") (pinfunction "VDD_54") (pintype "power_in"))
      (node (ref "U4") (pin "5") (pinfunction "VOUT_5") (pintype "passive"))
    )
    (net (code "51") (name "MOD-3V3") (class "Default")
      (node (ref "C10") (pin "1") (pinfunction "1_1") (pintype "passive"))
      (node (ref "C11") (pin "2") (pinfunction "2_2") (pintype "passive"))
      (node (ref "C18") (pin "2") (pinfunction "2_2") (pintype "passive"))
      (node (ref "C20") (pin "1") (pinfunction "1_1") (pintype "passive"))
      (node (ref "C21") (pin "1") (pinfunction "1_1") (pintype "passive"))
      (node (ref "C22") (pin "1") (pinfunction "1_1") (pintype "passive"))
      (node (ref "C23") (pin "1") (pinfunction "1_1") (pintype "passive"))
      (node (ref "C25") (pin "1") (pinfunction "1_1") (pintype "passive"))
      (node (ref "C26") (pin "1") (pinfunction "1_1") (pintype "passive"))
      (node (ref "U2") (pin "3") (pinfunction "WP(D1)_3") (pintype "passive"))
      (node (ref "U2") (pin "7") (pinfunction "HOLD(D3)_7") (pintype "passive"))
      (node (ref "U2") (pin "8") (pinfunction "VCC_8") (pintype "passive"))
      (node (ref "U5") (pin "5") (pinfunction "VOUT_5") (pintype "passive"))
      (node (ref "U6") (pin "1") (pinfunction "VDDIO_1") (pintype "passive"))
      (node (ref "U6") (pin "16") (pinfunction "VDD_16") (pintype "passive"))
      (node (ref "U7") (pin "6") (pinfunction "VDDIO_6") (pintype "passive"))
      (node (ref "U7") (pin "8") (pinfunction "VDD_8") (pintype "passive"))
      (node (ref "U8") (pin "16") (pinfunction "VDD_16") (pintype "passive"))
      (node (ref "U8") (pin "7") (pinfunction "VID_7") (pintype "passive"))
    )
    (net (code "52") (name "Net-(C4-Pad1)") (class "Default")
      (node (ref "C4") (pin "1") (pinfunction "1_1") (pintype "passive"))
      (node (ref "U3") (pin "25") (pinfunction "VDDC_25") (pintype "power_in"))
    )
    (net (code "53") (name "Net-(C5-Pad1)") (class "Default")
      (node (ref "C5") (pin "1") (pinfunction "1_1") (pintype "passive"))
      (node (ref "U3") (pin "56") (pinfunction "VDDC_56") (pintype "power_in"))
    )
    (net (code "54") (name "Net-(CON8-CC1(A5))") (class "Default")
      (node (ref "CON8") (pin "4") (pinfunction "CC1(A5)_4") (pintype "passive"))
      (node (ref "R14") (pin "2") (pinfunction "2_2") (pintype "passive"))
    )
    (net (code "55") (name "Net-(CON8-CC2(B5))") (class "Default")
      (node (ref "CON8") (pin "10") (pinfunction "CC2(B5)_10") (pintype "passive"))
      (node (ref "R15") (pin "2") (pinfunction "2_2") (pintype "passive"))
    )
    (net (code "56") (name "Net-(D2-K)") (class "Default")
      (node (ref "D2") (pin "2") (pinfunction "K_2") (pintype "passive"))
      (node (ref "R4") (pin "1") (pinfunction "1_1") (pintype "passive"))
    )
    (net (code "57") (name "Net-(D3-B)") (class "Default")
      (node (ref "D3") (pin "3") (pinfunction "B_3") (pintype "passive"))
      (node (ref "R8") (pin "2") (pinfunction "2_2") (pintype "passive"))
    )
    (net (code "58") (name "Net-(D3-G)") (class "Default")
      (node (ref "D3") (pin "2") (pinfunction "G_2") (pintype "passive"))
      (node (ref "R7") (pin "2") (pinfunction "2_2") (pintype "passive"))
    )
    (net (code "59") (name "Net-(D3-R)") (class "Default")
      (node (ref "D3") (pin "1") (pinfunction "R_1") (pintype "passive"))
      (node (ref "R6") (pin "2") (pinfunction "2_2") (pintype "passive"))
    )
    (net (code "60") (name "Net-(Q2-D)") (class "Default")
      (node (ref "Q2") (pin "3") (pinfunction "D_3") (pintype "passive"))
      (node (ref "R20") (pin "1") (pinfunction "1_1") (pintype "passive"))
    )
    (net (code "61") (name "Net-(R10-Pad2)") (class "Default")
      (node (ref "R10") (pin "2") (pinfunction "2_2") (pintype "passive"))
      (node (ref "R11") (pin "2") (pinfunction "2_2") (pintype "passive"))
      (node (ref "R9") (pin "1") (pinfunction "1_1") (pintype "passive"))
    )
    (net (code "62") (name "Net-(R16-Pad2)") (class "Default")
      (node (ref "R16") (pin "2") (pinfunction "2_2") (pintype "passive"))
      (node (ref "R17") (pin "2") (pinfunction "2_2") (pintype "passive"))
    )
    (net (code "63") (name "Net-(R17-Pad1)") (class "Default")
      (node (ref "R17") (pin "1") (pinfunction "1_1") (pintype "passive"))
      (node (ref "R19") (pin "1") (pinfunction "1_1") (pintype "passive"))
    )
    (net (code "64") (name "Net-(R19-Pad2)") (class "Default")
      (node (ref "R19") (pin "2") (pinfunction "2_2") (pintype "passive"))
      (node (ref "R20") (pin "2") (pinfunction "2_2") (pintype "passive"))
    )
    (net (code "65") (name "Net-(U1-BOOT)") (class "Default")
      (node (ref "C3") (pin "2") (pinfunction "2_2") (pintype "passive"))
      (node (ref "U1") (pin "6") (pinfunction "BOOT_6") (pintype "passive"))
    )
    (net (code "66") (name "Net-(U1-FB)") (class "Default")
      (node (ref "C7") (pin "2") (pinfunction "2_2") (pintype "passive"))
      (node (ref "R2") (pin "1") (pinfunction "1_1") (pintype "passive"))
      (node (ref "R3") (pin "2") (pinfunction "2_2") (pintype "passive"))
      (node (ref "U1") (pin "4") (pinfunction "FB_4") (pintype "passive"))
    )
    (net (code "67") (name "Net-(U1-SW)") (class "Default")
      (node (ref "C3") (pin "1") (pinfunction "1_1") (pintype "passive"))
      (node (ref "L1") (pin "1") (pinfunction "1_1") (pintype "passive"))
      (node (ref "U1") (pin "2") (pinfunction "SW_2") (pintype "passive"))
    )
    (net (code "68") (name "Net-(U3A-*WAKE)") (class "Default")
      (node (ref "R5") (pin "2") (pinfunction "2_2") (pintype "passive"))
      (node (ref "U3") (pin "32") (pinfunction "*WAKE_32") (pintype "input"))
    )
    (net (code "69") (name "Net-(U6-REGOUT)") (class "Default")
      (node (ref "C24") (pin "2") (pinfunction "2_2") (pintype "passive"))
      (node (ref "U6") (pin "14") (pinfunction "REGOUT_14") (pintype "passive"))
    )
    (net (code "70") (name "VBUS") (class "Default")
      (node (ref "CON8") (pin "11") (pinfunction "VBUS(A9B4)_11") (pintype "passive"))
      (node (ref "CON8") (pin "2") (pinfunction "VBUS(A4B9)_2") (pintype "passive"))
      (node (ref "D4") (pin "1") (pinfunction "A_1") (pintype "passive"))
      (node (ref "U9") (pin "5") (pinfunction "VBUS_5") (pintype "passive"))
    )
    (net (code "71") (name "VCC") (class "Default")
      (node (ref "C1") (pin "2") (pinfunction "2_2") (pintype "passive"))
      (node (ref "CON6") (pin "1") (pinfunction "1_1") (pintype "passive"))
      (node (ref "CON6") (pin "4") (pinfunction "4_4") (pintype "passive"))
      (node (ref "D1") (pin "2") (pinfunction "A_2") (pintype "passive"))
      (node (ref "R9") (pin "2") (pinfunction "2_2") (pintype "passive"))
      (node (ref "U1") (pin "3") (pinfunction "VIN_3") (pintype "passive"))
    )
    (net (code "72") (name "unconnected-(CON1-Pad5)") (class "Default")
      (node (ref "CON1") (pin "5") (pinfunction "5_5") (pintype "passive+no_connect"))
    )
    (net (code "73") (name "unconnected-(CON1-Pad6)") (class "Default")
      (node (ref "CON1") (pin "6") (pinfunction "6_6") (pintype "passive+no_connect"))
    )
    (net (code "74") (name "unconnected-(CON2-Pad5)") (class "Default")
      (node (ref "CON2") (pin "5") (pinfunction "5_5") (pintype "passive+no_connect"))
    )
    (net (code "75") (name "unconnected-(CON2-Pad6)") (class "Default")
      (node (ref "CON2") (pin "6") (pinfunction "6_6") (pintype "passive+no_connect"))
    )
    (net (code "76") (name "unconnected-(CON3-Pad5)") (class "Default")
      (node (ref "CON3") (pin "5") (pinfunction "5_5") (pintype "passive+no_connect"))
    )
    (net (code "77") (name "unconnected-(CON3-Pad6)") (class "Default")
      (node (ref "CON3") (pin "6") (pinfunction "6_6") (pintype "passive+no_connect"))
    )
    (net (code "78") (name "unconnected-(CON4-Pad5)") (class "Default")
      (node (ref "CON4") (pin "5") (pinfunction "5_5") (pintype "passive+no_connect"))
    )
    (net (code "79") (name "unconnected-(CON4-Pad6)") (class "Default")
      (node (ref "CON4") (pin "6") (pinfunction "6_6") (pintype "passive+no_connect"))
    )
    (net (code "80") (name "unconnected-(CON5-Pad5)") (class "Default")
      (node (ref "CON5") (pin "5") (pinfunction "5_5") (pintype "passive+no_connect"))
    )
    (net (code "81") (name "unconnected-(CON5-Pad6)") (class "Default")
      (node (ref "CON5") (pin "6") (pinfunction "6_6") (pintype "passive+no_connect"))
    )
    (net (code "82") (name "unconnected-(CON7-Pad5)") (class "Default")
      (node (ref "CON7") (pin "5") (pinfunction "5_5") (pintype "passive+no_connect"))
    )
    (net (code "83") (name "unconnected-(CON7-Pad6)") (class "Default")
      (node (ref "CON7") (pin "6") (pinfunction "6_6") (pintype "passive+no_connect"))
    )
    (net (code "84") (name "unconnected-(CON8-SBU1(A8)-Pad9)") (class "Default")
      (node (ref "CON8") (pin "9") (pinfunction "SBU1(A8)_9") (pintype "passive+no_connect"))
    )
    (net (code "85") (name "unconnected-(CON8-SBU2(B8)-Pad3)") (class "Default")
      (node (ref "CON8") (pin "3") (pinfunction "SBU2(B8)_3") (pintype "passive+no_connect"))
    )
    (net (code "86") (name "unconnected-(CON8-SH-Pad0)") (class "Default")
      (node (ref "CON8") (pin "0") (pinfunction "SH_0") (pintype "passive"))
    )
    (net (code "87") (name "unconnected-(P1-Pad11)") (class "Default")
      (node (ref "P1") (pin "11") (pinfunction "11_11") (pintype "passive"))
    )
    (net (code "88") (name "unconnected-(P1-Pad12)") (class "Default")
      (node (ref "P1") (pin "12") (pinfunction "12_12") (pintype "passive"))
    )
    (net (code "89") (name "unconnected-(U1-EN-Pad5)") (class "Default")
      (node (ref "U1") (pin "5") (pinfunction "EN_5") (pintype "passive+no_connect"))
    )
    (net (code "90") (name "unconnected-(U1-Pad7)") (class "Default")
      (node (ref "U1") (pin "7") (pintype "passive"))
    )
    (net (code "91") (name "unconnected-(U3A-*HIB-Pad33)") (class "Default")
      (node (ref "U3") (pin "33") (pinfunction "*HIB_33") (pintype "output+no_connect"))
    )
    (net (code "92") (name "unconnected-(U3A-XOSC1-Pad36)") (class "Default")
      (node (ref "U3") (pin "36") (pinfunction "XOSC1_36") (pintype "output+no_connect"))
    )
    (net (code "93") (name "unconnected-(U3B-PB0{slash}USB0ID-Pad45)") (class "Default")
      (node (ref "U3") (pin "45") (pinfunction "PB0/USB0ID_45") (pintype "bidirectional+no_connect"))
    )
    (net (code "94") (name "unconnected-(U3B-PB1{slash}USB0VBUS-Pad46)") (class "Default")
      (node (ref "U3") (pin "46") (pinfunction "PB1/USB0VBUS_46") (pintype "bidirectional+no_connect"))
    )
    (net (code "95") (name "unconnected-(U3B-PB2{slash}I2C0SCL-Pad47)") (class "Default")
      (node (ref "U3") (pin "47") (pinfunction "PB2/I2C0SCL_47") (pintype "bidirectional+no_connect"))
    )
    (net (code "96") (name "unconnected-(U3B-PB3{slash}I2C0SDA-Pad48)") (class "Default")
      (node (ref "U3") (pin "48") (pinfunction "PB3/I2C0SDA_48") (pintype "bidirectional+no_connect"))
    )
    (net (code "97") (name "unconnected-(U4-NC-Pad4)") (class "Default")
      (node (ref "U4") (pin "4") (pinfunction "NC_4") (pintype "passive+no_connect"))
    )
    (net (code "98") (name "unconnected-(U5-NC-Pad4)") (class "Default")
      (node (ref "U5") (pin "4") (pinfunction "NC_4") (pintype "passive+no_connect"))
    )
    (net (code "99") (name "unconnected-(U6-RESV-Pad7)") (class "Default")
      (node (ref "U6") (pin "7") (pinfunction "RESV_7") (pintype "passive+no_connect"))
    )
    (net (code "100") (name "unconnected-(U8-NC1-Pad8)") (class "Default")
      (node (ref "U8") (pin "8") (pinfunction "NC1_8") (pintype "passive+no_connect"))
    )
    (net (code "101") (name "unconnected-(U8-NC2-Pad12)") (class "Default")
      (node (ref "U8") (pin "12") (pinfunction "NC2_12") (pintype "passive+no_connect"))
    )
    (net (code "102") (name "unconnected-(U8-RSV-Pad3)") (class "Default")
      (node (ref "U8") (pin "3") (pinfunction "RSV_3") (pintype "passive+no_connect"))
    )
    (net (code "103") (name "unconnected-(U8-TST1-Pad1)") (class "Default")
      (node (ref "U8") (pin "1") (pinfunction "TST1_1") (pintype "passive+no_connect"))
    )
    (net (code "104") (name "unconnected-(U8-TST2-Pad14)") (class "Default")
      (node (ref "U8") (pin "14") (pinfunction "TST2_14") (pintype "passive+no_connect"))
    )
    (net (code "105") (name "unconnected-(U8-TST6-Pad9)") (class "Default")
      (node (ref "U8") (pin "9") (pinfunction "TST6_9") (pintype "passive+no_connect"))
    )
  )
)
